# stage_light.net
KiCad netlist of a schematic drawn in EAGLE
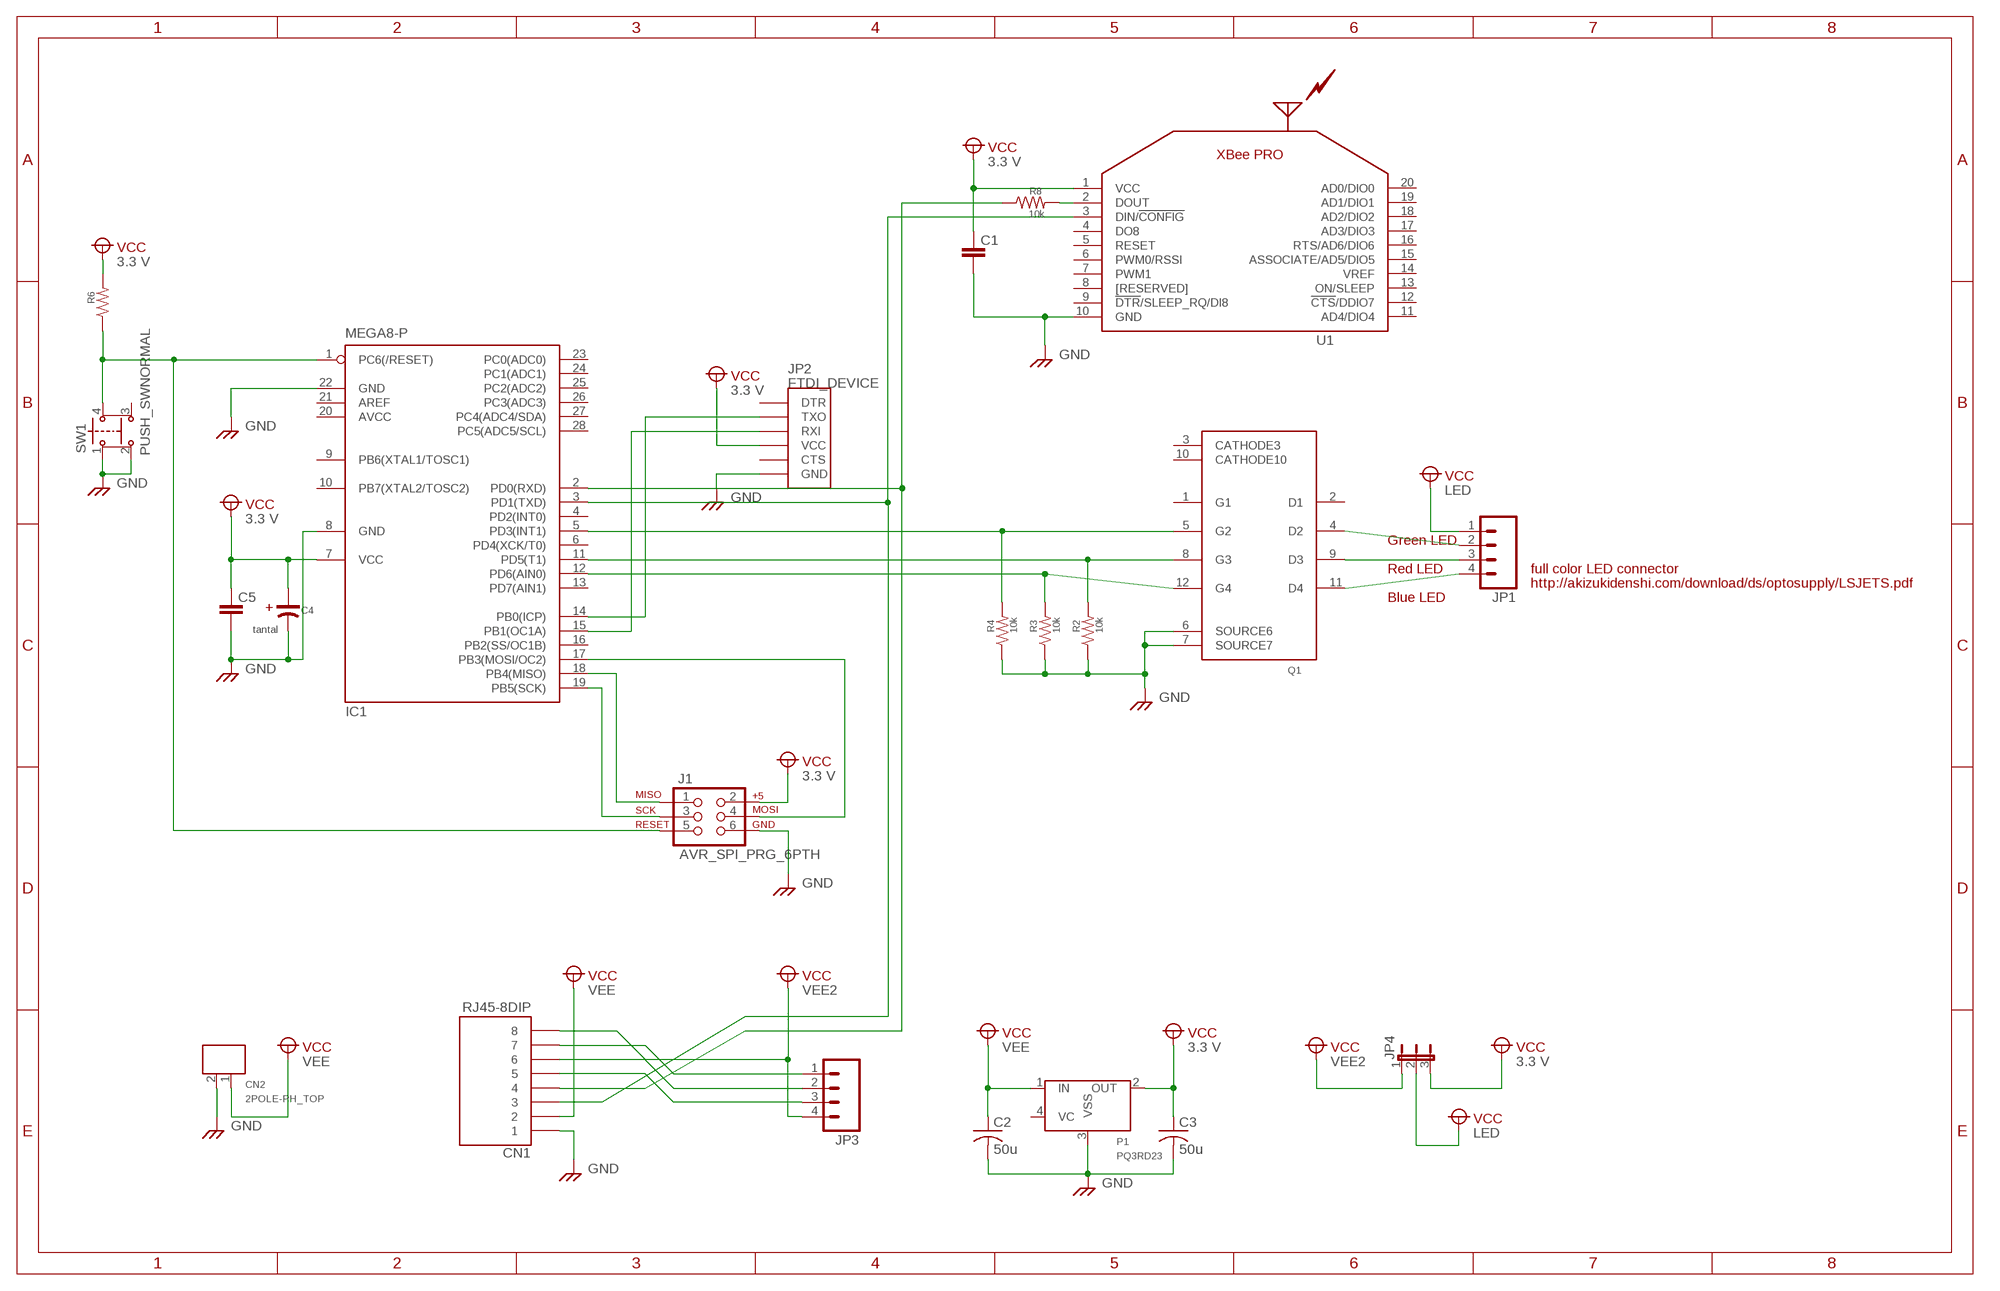
[diagram p0: schematic, sheet 1]

(export (version "E")
  (design (tool "Eeschema 10.0.6"))
  (components
    (comp (ref "C1")
      (value "GRM18")
      (footprint "eagle-import:1608(1.6_0.8MM)")
      (libsource (lib "eagle-import") (part "GRM18"))
    )
    (comp (ref "C2")
      (value "50u")
      (footprint "eagle-import:C025-050X050")
      (libsource (lib "eagle-import") (part "C-US025-050X050"))
    )
    (comp (ref "C3")
      (value "50u")
      (footprint "eagle-import:C025-050X050")
      (libsource (lib "eagle-import") (part "C-US025-050X050"))
    )
    (comp (ref "C4")
      (value "CT-100U")
      (footprint "eagle-import:6134(6.1_3.4MM)_POLAR")
      (libsource (lib "eagle-import") (part "CT-100U"))
    )
    (comp (ref "C5")
      (value "GRM18")
      (footprint "eagle-import:1608(1.6_0.8MM)")
      (libsource (lib "eagle-import") (part "GRM18"))
    )
    (comp (ref "CN1")
      (value "RJ45-8DIP")
      (footprint "eagle-import:AE-RJ-45-LAN-DIP-A")
      (libsource (lib "eagle-import") (part "RJ45-8DIP"))
    )
    (comp (ref "CN2")
      (value "2POLE-PH_TOP")
      (footprint "eagle-import:B2B-PH-K-S(2MM_PITCH)")
      (libsource (lib "eagle-import") (part "2POLE-PH_TOP"))
    )
    (comp (ref "IC1")
      (value "MEGA8-P")
      (footprint "eagle-import:DIL28-3")
      (libsource (lib "eagle-import") (part "MEGA8-P"))
    )
    (comp (ref "J1")
      (value "AVR_SPI_PRG_6PTH")
      (footprint "eagle-import:2X3")
      (libsource (lib "eagle-import") (part "AVR_SPI_PRG_6PTH"))
    )
    (comp (ref "JP1")
      (value "M04LONGPADS")
      (footprint "eagle-import:1X04_LONGPADS")
      (libsource (lib "eagle-import") (part "M04LONGPADS"))
    )
    (comp (ref "JP2")
      (value "FTDI_DEVICE")
      (footprint "eagle-import:FTDI_DEVICE_SIDE")
      (libsource (lib "eagle-import") (part "FTDI_DEVICE"))
    )
    (comp (ref "JP3")
      (value "M04PTH")
      (footprint "eagle-import:1X04")
      (libsource (lib "eagle-import") (part "M04PTH"))
    )
    (comp (ref "JP4")
      (value "JP2E")
      (footprint "eagle-import:JP2")
      (libsource (lib "eagle-import") (part "JP2E"))
    )
    (comp (ref "P1")
      (value "PQ3RD23")
      (footprint "eagle-import:PQ3RD23")
      (libsource (lib "eagle-import") (part "PQ3RD23"))
    )
    (comp (ref "Q1")
      (value "MP4401")
      (footprint "eagle-import:MP4401")
      (libsource (lib "eagle-import") (part "MP4401"))
    )
    (comp (ref "R2")
      (value "10k")
      (footprint "eagle-import:1608(1.6_0.8MM)")
      (libsource (lib "eagle-import") (part "CHIP1608"))
    )
    (comp (ref "R3")
      (value "10k")
      (footprint "eagle-import:1608(1.6_0.8MM)")
      (libsource (lib "eagle-import") (part "CHIP1608"))
    )
    (comp (ref "R4")
      (value "10k")
      (footprint "eagle-import:1608(1.6_0.8MM)")
      (libsource (lib "eagle-import") (part "CHIP1608"))
    )
    (comp (ref "R6")
      (value "CHIP1608")
      (footprint "eagle-import:1608(1.6_0.8MM)")
      (libsource (lib "eagle-import") (part "CHIP1608"))
    )
    (comp (ref "R8")
      (value "10k")
      (footprint "eagle-import:1608(1.6_0.8MM)")
      (libsource (lib "eagle-import") (part "CHIP1608"))
    )
    (comp (ref "SW1")
      (value "PUSH_SWNORMAL")
      (footprint "eagle-import:PUSH_SW")
      (libsource (lib "eagle-import") (part "PUSH_SWNORMAL"))
    )
    (comp (ref "U1")
      (value "XBEE_PROXPPN101BFCN")
      (footprint "eagle-import:XBEE_ON_XPPN101BFCN-RC")
      (libsource (lib "eagle-import") (part "XBEE_PROXPPN101BFCN"))
    )
  )
  (nets
    (net (code "1") (name "/AVCC") (class "Default")
      (node (ref "IC1") (pin "20") (pinfunction "AVCC_20") (pintype "power_in"))
    )
    (net (code "2") (name "3.3 V") (class "Default")
      (node (ref "C1") (pin "P$1") (pinfunction "1_P$1") (pintype "passive"))
      (node (ref "C3") (pin "1") (pinfunction "1_1") (pintype "passive"))
      (node (ref "C4") (pin "+") (pinfunction "+_+") (pintype "passive"))
      (node (ref "C5") (pin "P$1") (pinfunction "1_P$1") (pintype "passive"))
      (node (ref "IC1") (pin "7") (pinfunction "VCC_7") (pintype "power_in"))
      (node (ref "J1") (pin "2") (pinfunction "2_2") (pintype "passive"))
      (node (ref "JP2") (pin "P$4") (pinfunction "VCC_P$4") (pintype "bidirectional"))
      (node (ref "JP4") (pin "3") (pinfunction "3_3") (pintype "passive"))
      (node (ref "P1") (pin "2") (pinfunction "OUT_2") (pintype "bidirectional"))
      (node (ref "R6") (pin "P$4") (pinfunction "2_P$4") (pintype "passive"))
      (node (ref "U1") (pin "1") (pinfunction "VCC_1") (pintype "bidirectional"))
    )
    (net (code "3") (name "GND") (class "Default")
      (node (ref "C1") (pin "P$2") (pinfunction "2_P$2") (pintype "passive"))
      (node (ref "C2") (pin "2") (pinfunction "2_2") (pintype "passive"))
      (node (ref "C3") (pin "2") (pinfunction "2_2") (pintype "passive"))
      (node (ref "C4") (pin "-") (pinfunction "-_-") (pintype "passive"))
      (node (ref "C5") (pin "P$2") (pinfunction "2_P$2") (pintype "passive"))
      (node (ref "CN1") (pin "1") (pinfunction "1_1") (pintype "bidirectional"))
      (node (ref "CN2") (pin "2") (pinfunction "P$2_2") (pintype "bidirectional"))
      (node (ref "IC1") (pin "22") (pinfunction "GND_22") (pintype "power_in"))
      (node (ref "IC1") (pin "8") (pinfunction "GND_8") (pintype "power_in"))
      (node (ref "J1") (pin "6") (pinfunction "6_6") (pintype "passive"))
      (node (ref "JP2") (pin "P$6") (pinfunction "GND_P$6") (pintype "bidirectional"))
      (node (ref "P1") (pin "3") (pinfunction "VSS_3") (pintype "bidirectional"))
      (node (ref "Q1") (pin "6") (pinfunction "SOURCE6_6") (pintype "power_in"))
      (node (ref "Q1") (pin "7") (pinfunction "SOURCE7_7") (pintype "power_in"))
      (node (ref "R2") (pin "P$3") (pinfunction "1_P$3") (pintype "passive"))
      (node (ref "R3") (pin "P$3") (pinfunction "1_P$3") (pintype "passive"))
      (node (ref "R4") (pin "P$3") (pinfunction "1_P$3") (pintype "passive"))
      (node (ref "SW1") (pin "1") (pinfunction "P1_1") (pintype "bidirectional"))
      (node (ref "SW1") (pin "2") (pinfunction "P2_2") (pintype "bidirectional"))
      (node (ref "U1") (pin "10") (pinfunction "GND_10") (pintype "bidirectional"))
    )
    (net (code "4") (name "LED") (class "Default")
      (node (ref "JP1") (pin "1") (pinfunction "1_1") (pintype "passive"))
      (node (ref "JP4") (pin "2") (pinfunction "2_2") (pintype "passive"))
    )
    (net (code "5") (name "Net-(CN1-Pad5)") (class "Default")
      (node (ref "CN1") (pin "5") (pinfunction "5_5") (pintype "bidirectional"))
      (node (ref "JP3") (pin "3") (pinfunction "3_3") (pintype "passive"))
    )
    (net (code "6") (name "Net-(CN1-Pad7)") (class "Default")
      (node (ref "CN1") (pin "7") (pinfunction "7_7") (pintype "bidirectional"))
      (node (ref "JP3") (pin "1") (pinfunction "1_1") (pintype "passive"))
    )
    (net (code "7") (name "Net-(CN1-Pad8)") (class "Default")
      (node (ref "CN1") (pin "8") (pinfunction "8_8") (pintype "bidirectional"))
      (node (ref "JP3") (pin "2") (pinfunction "2_2") (pintype "passive"))
    )
    (net (code "8") (name "Net-(IC1-PB0(ICP))") (class "Default")
      (node (ref "IC1") (pin "14") (pinfunction "PB0(ICP)_14") (pintype "bidirectional"))
      (node (ref "JP2") (pin "P$2") (pinfunction "TXO_P$2") (pintype "bidirectional"))
    )
    (net (code "9") (name "Net-(IC1-PB1(OC1A))") (class "Default")
      (node (ref "IC1") (pin "15") (pinfunction "PB1(OC1A)_15") (pintype "bidirectional"))
      (node (ref "JP2") (pin "P$3") (pinfunction "RXI_P$3") (pintype "bidirectional"))
    )
    (net (code "10") (name "Net-(IC1-PB3(MOSI{slash}OC2))") (class "Default")
      (node (ref "IC1") (pin "17") (pinfunction "PB3(MOSI/OC2)_17") (pintype "bidirectional"))
      (node (ref "J1") (pin "4") (pinfunction "4_4") (pintype "passive"))
    )
    (net (code "11") (name "Net-(IC1-PB4(MISO))") (class "Default")
      (node (ref "IC1") (pin "18") (pinfunction "PB4(MISO)_18") (pintype "bidirectional"))
      (node (ref "J1") (pin "1") (pinfunction "1_1") (pintype "passive"))
    )
    (net (code "12") (name "Net-(IC1-PB5(SCK))") (class "Default")
      (node (ref "IC1") (pin "19") (pinfunction "PB5(SCK)_19") (pintype "bidirectional"))
      (node (ref "J1") (pin "3") (pinfunction "3_3") (pintype "passive"))
    )
    (net (code "13") (name "Net-(IC1-PC6({slash}RESET))") (class "Default")
      (node (ref "IC1") (pin "1") (pinfunction "PC6(/RESET)_1") (pintype "bidirectional"))
      (node (ref "J1") (pin "5") (pinfunction "5_5") (pintype "passive"))
      (node (ref "R6") (pin "P$3") (pinfunction "1_P$3") (pintype "passive"))
      (node (ref "SW1") (pin "4") (pinfunction "P3_4") (pintype "bidirectional"))
    )
    (net (code "14") (name "Net-(IC1-PD0(RXD))") (class "Default")
      (node (ref "CN1") (pin "4") (pinfunction "4_4") (pintype "bidirectional"))
      (node (ref "IC1") (pin "2") (pinfunction "PD0(RXD)_2") (pintype "bidirectional"))
      (node (ref "R8") (pin "P$3") (pinfunction "1_P$3") (pintype "passive"))
    )
    (net (code "15") (name "Net-(IC1-PD1(TXD))") (class "Default")
      (node (ref "CN1") (pin "3") (pinfunction "3_3") (pintype "bidirectional"))
      (node (ref "IC1") (pin "3") (pinfunction "PD1(TXD)_3") (pintype "bidirectional"))
      (node (ref "U1") (pin "3") (pinfunction "DIN/~{CONFIG}_3") (pintype "bidirectional"))
    )
    (net (code "16") (name "Net-(IC1-PD3(INT1))") (class "Default")
      (node (ref "IC1") (pin "5") (pinfunction "PD3(INT1)_5") (pintype "bidirectional"))
      (node (ref "Q1") (pin "5") (pinfunction "G2_5") (pintype "bidirectional"))
      (node (ref "R4") (pin "P$4") (pinfunction "2_P$4") (pintype "passive"))
    )
    (net (code "17") (name "Net-(IC1-PD5(T1))") (class "Default")
      (node (ref "IC1") (pin "11") (pinfunction "PD5(T1)_11") (pintype "bidirectional"))
      (node (ref "Q1") (pin "8") (pinfunction "G3_8") (pintype "bidirectional"))
      (node (ref "R2") (pin "P$4") (pinfunction "2_P$4") (pintype "passive"))
    )
    (net (code "18") (name "Net-(IC1-PD6(AIN0))") (class "Default")
      (node (ref "IC1") (pin "12") (pinfunction "PD6(AIN0)_12") (pintype "bidirectional"))
      (node (ref "Q1") (pin "12") (pinfunction "G4_12") (pintype "bidirectional"))
      (node (ref "R3") (pin "P$4") (pinfunction "2_P$4") (pintype "passive"))
    )
    (net (code "19") (name "Net-(Q1-D2)") (class "Default")
      (node (ref "JP1") (pin "2") (pinfunction "2_2") (pintype "passive"))
      (node (ref "Q1") (pin "4") (pinfunction "D2_4") (pintype "bidirectional"))
    )
    (net (code "20") (name "Net-(Q1-D3)") (class "Default")
      (node (ref "JP1") (pin "3") (pinfunction "3_3") (pintype "passive"))
      (node (ref "Q1") (pin "9") (pinfunction "D3_9") (pintype "bidirectional"))
    )
    (net (code "21") (name "Net-(Q1-D4)") (class "Default")
      (node (ref "JP1") (pin "4") (pinfunction "4_4") (pintype "passive"))
      (node (ref "Q1") (pin "11") (pinfunction "D4_11") (pintype "bidirectional"))
    )
    (net (code "22") (name "Net-(R8-2)") (class "Default")
      (node (ref "R8") (pin "P$4") (pinfunction "2_P$4") (pintype "passive"))
      (node (ref "U1") (pin "2") (pinfunction "DOUT_2") (pintype "bidirectional"))
    )
    (net (code "23") (name "VEE") (class "Default")
      (node (ref "C2") (pin "1") (pinfunction "1_1") (pintype "passive"))
      (node (ref "CN1") (pin "2") (pinfunction "2_2") (pintype "bidirectional"))
      (node (ref "CN2") (pin "1") (pinfunction "P$1_1") (pintype "bidirectional"))
      (node (ref "P1") (pin "1") (pinfunction "IN_1") (pintype "bidirectional"))
    )
    (net (code "24") (name "VEE2") (class "Default")
      (node (ref "CN1") (pin "6") (pinfunction "6_6") (pintype "bidirectional"))
      (node (ref "JP3") (pin "4") (pinfunction "4_4") (pintype "passive"))
      (node (ref "JP4") (pin "1") (pinfunction "1_1") (pintype "passive"))
    )
    (net (code "25") (name "unconnected-(IC1-AREF-Pad21)") (class "Default")
      (node (ref "IC1") (pin "21") (pinfunction "AREF_21") (pintype "passive"))
    )
    (net (code "26") (name "unconnected-(IC1-PB2(SS{slash}OC1B)-Pad16)") (class "Default")
      (node (ref "IC1") (pin "16") (pinfunction "PB2(SS/OC1B)_16") (pintype "bidirectional"))
    )
    (net (code "27") (name "unconnected-(IC1-PB6(XTAL1{slash}TOSC1)-Pad9)") (class "Default")
      (node (ref "IC1") (pin "9") (pinfunction "PB6(XTAL1/TOSC1)_9") (pintype "bidirectional"))
    )
    (net (code "28") (name "unconnected-(IC1-PB7(XTAL2{slash}TOSC2)-Pad10)") (class "Default")
      (node (ref "IC1") (pin "10") (pinfunction "PB7(XTAL2/TOSC2)_10") (pintype "bidirectional"))
    )
    (net (code "29") (name "unconnected-(IC1-PC0(ADC0)-Pad23)") (class "Default")
      (node (ref "IC1") (pin "23") (pinfunction "PC0(ADC0)_23") (pintype "bidirectional"))
    )
    (net (code "30") (name "unconnected-(IC1-PC1(ADC1)-Pad24)") (class "Default")
      (node (ref "IC1") (pin "24") (pinfunction "PC1(ADC1)_24") (pintype "bidirectional"))
    )
    (net (code "31") (name "unconnected-(IC1-PC2(ADC2)-Pad25)") (class "Default")
      (node (ref "IC1") (pin "25") (pinfunction "PC2(ADC2)_25") (pintype "bidirectional"))
    )
    (net (code "32") (name "unconnected-(IC1-PC3(ADC3)-Pad26)") (class "Default")
      (node (ref "IC1") (pin "26") (pinfunction "PC3(ADC3)_26") (pintype "bidirectional"))
    )
    (net (code "33") (name "unconnected-(IC1-PC4(ADC4{slash}SDA)-Pad27)") (class "Default")
      (node (ref "IC1") (pin "27") (pinfunction "PC4(ADC4/SDA)_27") (pintype "bidirectional"))
    )
    (net (code "34") (name "unconnected-(IC1-PC5(ADC5{slash}SCL)-Pad28)") (class "Default")
      (node (ref "IC1") (pin "28") (pinfunction "PC5(ADC5/SCL)_28") (pintype "bidirectional"))
    )
    (net (code "35") (name "unconnected-(IC1-PD2(INT0)-Pad4)") (class "Default")
      (node (ref "IC1") (pin "4") (pinfunction "PD2(INT0)_4") (pintype "bidirectional"))
    )
    (net (code "36") (name "unconnected-(IC1-PD4(XCK{slash}T0)-Pad6)") (class "Default")
      (node (ref "IC1") (pin "6") (pinfunction "PD4(XCK/T0)_6") (pintype "bidirectional"))
    )
    (net (code "37") (name "unconnected-(IC1-PD7(AIN1)-Pad13)") (class "Default")
      (node (ref "IC1") (pin "13") (pinfunction "PD7(AIN1)_13") (pintype "bidirectional"))
    )
    (net (code "38") (name "unconnected-(JP2-CTS-PadP$5)") (class "Default")
      (node (ref "JP2") (pin "P$5") (pinfunction "CTS_P$5") (pintype "bidirectional"))
    )
    (net (code "39") (name "unconnected-(JP2-DTR-PadP$1)") (class "Default")
      (node (ref "JP2") (pin "P$1") (pinfunction "DTR_P$1") (pintype "bidirectional"))
    )
    (net (code "40") (name "unconnected-(P1-VC-Pad4)") (class "Default")
      (node (ref "P1") (pin "4") (pinfunction "VC_4") (pintype "bidirectional"))
    )
    (net (code "41") (name "unconnected-(Q1-CATHODE3-Pad3)") (class "Default")
      (node (ref "Q1") (pin "3") (pinfunction "CATHODE3_3") (pintype "bidirectional"))
    )
    (net (code "42") (name "unconnected-(Q1-CATHODE10-Pad10)") (class "Default")
      (node (ref "Q1") (pin "10") (pinfunction "CATHODE10_10") (pintype "bidirectional"))
    )
    (net (code "43") (name "unconnected-(Q1-D1-Pad2)") (class "Default")
      (node (ref "Q1") (pin "2") (pinfunction "D1_2") (pintype "bidirectional"))
    )
    (net (code "44") (name "unconnected-(Q1-G1-Pad1)") (class "Default")
      (node (ref "Q1") (pin "1") (pinfunction "G1_1") (pintype "bidirectional"))
    )
    (net (code "45") (name "unconnected-(SW1-P4-Pad3)") (class "Default")
      (node (ref "SW1") (pin "3") (pinfunction "P4_3") (pintype "bidirectional"))
    )
    (net (code "46") (name "unconnected-(U1-AD0{slash}DIO0-Pad20)") (class "Default")
      (node (ref "U1") (pin "20") (pinfunction "AD0/DIO0_20") (pintype "bidirectional"))
    )
    (net (code "47") (name "unconnected-(U1-AD1{slash}DIO1-Pad19)") (class "Default")
      (node (ref "U1") (pin "19") (pinfunction "AD1/DIO1_19") (pintype "bidirectional"))
    )
    (net (code "48") (name "unconnected-(U1-AD2{slash}DIO2-Pad18)") (class "Default")
      (node (ref "U1") (pin "18") (pinfunction "AD2/DIO2_18") (pintype "bidirectional"))
    )
    (net (code "49") (name "unconnected-(U1-AD3{slash}DIO3-Pad17)") (class "Default")
      (node (ref "U1") (pin "17") (pinfunction "AD3/DIO3_17") (pintype "bidirectional"))
    )
    (net (code "50") (name "unconnected-(U1-AD4{slash}DIO4-Pad11)") (class "Default")
      (node (ref "U1") (pin "11") (pinfunction "AD4/DIO4_11") (pintype "bidirectional"))
    )
    (net (code "51") (name "unconnected-(U1-ASSOCIATE{slash}AD5{slash}DIO5-Pad15)") (class "Default")
      (node (ref "U1") (pin "15") (pinfunction "ASSOCIATE/AD5/DIO5_15") (pintype "bidirectional"))
    )
    (net (code "52") (name "unconnected-(U1-DO8-Pad4)") (class "Default")
      (node (ref "U1") (pin "4") (pinfunction "DO8_4") (pintype "bidirectional"))
    )
    (net (code "53") (name "unconnected-(U1-ON{slash}SLEEP-Pad13)") (class "Default")
      (node (ref "U1") (pin "13") (pinfunction "ON/SLEEP_13") (pintype "bidirectional"))
    )
    (net (code "54") (name "unconnected-(U1-PWM0{slash}RSSI-Pad6)") (class "Default")
      (node (ref "U1") (pin "6") (pinfunction "PWM0/RSSI_6") (pintype "bidirectional"))
    )
    (net (code "55") (name "unconnected-(U1-PWM1-Pad7)") (class "Default")
      (node (ref "U1") (pin "7") (pinfunction "PWM1_7") (pintype "bidirectional"))
    )
    (net (code "56") (name "unconnected-(U1-RESET-Pad5)") (class "Default")
      (node (ref "U1") (pin "5") (pinfunction "RESET_5") (pintype "bidirectional"))
    )
    (net (code "57") (name "unconnected-(U1-RTS{slash}AD6{slash}DIO6-Pad16)") (class "Default")
      (node (ref "U1") (pin "16") (pinfunction "RTS/AD6/DIO6_16") (pintype "bidirectional"))
    )
    (net (code "58") (name "unconnected-(U1-VREF-Pad14)") (class "Default")
      (node (ref "U1") (pin "14") (pinfunction "VREF_14") (pintype "bidirectional"))
    )
    (net (code "59") (name "unconnected-(U1-[RESERVED]-Pad8)") (class "Default")
      (node (ref "U1") (pin "8") (pinfunction "[RESERVED]_8") (pintype "bidirectional"))
    )
    (net (code "60") (name "unconnected-(U1-~{CTS}{slash}DDIO7-Pad12)") (class "Default")
      (node (ref "U1") (pin "12") (pinfunction "~{CTS}/DDIO7_12") (pintype "bidirectional"))
    )
    (net (code "61") (name "unconnected-(U1-~{DTR}{slash}SLEEP_RQ{slash}DI8-Pad9)") (class "Default")
      (node (ref "U1") (pin "9") (pinfunction "~{DTR}/SLEEP_RQ/DI8_9") (pintype "bidirectional"))
    )
  )
)
